# Main.net
KiCad netlist of a schematic drawn in EAGLE
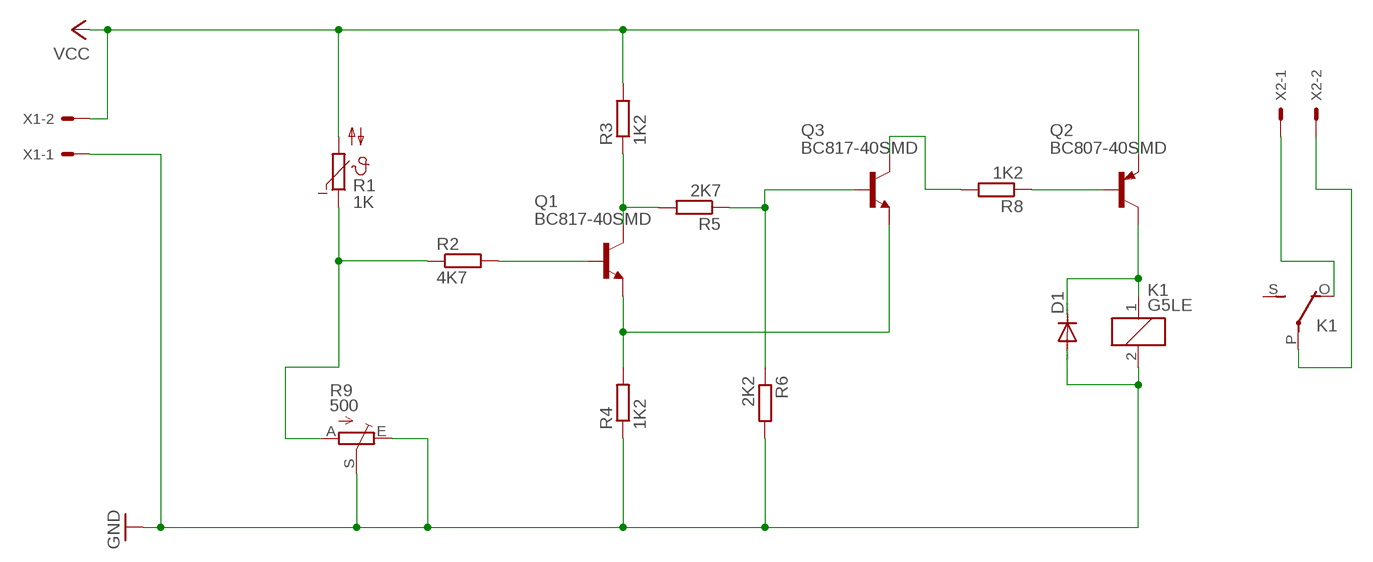
[diagram p0: schematic, sheet 1]

(export (version "E")
  (design (tool "Eeschema 10.0.6"))
  (components
    (comp (ref "D1")
      (value "DIODE-DO214AC")
      (footprint "eagle-import:DO214AC")
      (libsource (lib "eagle-import") (part "DIODE-DO214AC"))
    )
    (comp (ref "K1")
      (value "G5LE")
      (footprint "eagle-import:G5LE")
      (libsource (lib "eagle-import") (part "G5LE"))
    )
    (comp (ref "Q1")
      (value "BC817-40SMD")
      (footprint "eagle-import:SOT23-BEC")
      (libsource (lib "eagle-import") (part "BC817SMD-40"))
    )
    (comp (ref "Q2")
      (value "BC807-40SMD")
      (footprint "eagle-import:SOT23-BEC")
      (libsource (lib "eagle-import") (part "BC807SMD-40"))
    )
    (comp (ref "Q3")
      (value "BC817-40SMD")
      (footprint "eagle-import:SOT23-BEC")
      (libsource (lib "eagle-import") (part "BC817SMD-40"))
    )
    (comp (ref "R1")
      (value "1K")
      (footprint "eagle-import:B57164")
      (fields (field (name "MPN") "B57164K474K52"))
      (libsource (lib "eagle-import") (part "B57164"))
    )
    (comp (ref "R2")
      (value "4K7")
      (footprint "eagle-import:R1206")
      (libsource (lib "eagle-import") (part "R-EU_R1206"))
    )
    (comp (ref "R3")
      (value "1K2")
      (footprint "eagle-import:R1206")
      (libsource (lib "eagle-import") (part "R-EU_R1206"))
    )
    (comp (ref "R4")
      (value "1K2")
      (footprint "eagle-import:R1206")
      (libsource (lib "eagle-import") (part "R-EU_R1206"))
    )
    (comp (ref "R5")
      (value "2K7")
      (footprint "eagle-import:R1206")
      (libsource (lib "eagle-import") (part "R-EU_R1206"))
    )
    (comp (ref "R6")
      (value "2K2")
      (footprint "eagle-import:R1206")
      (libsource (lib "eagle-import") (part "R-EU_R1206"))
    )
    (comp (ref "R8")
      (value "1K2")
      (footprint "eagle-import:R1206")
      (libsource (lib "eagle-import") (part "R-EU_R1206"))
    )
    (comp (ref "R9")
      (value "500")
      (footprint "eagle-import:CA14V")
      (libsource (lib "eagle-import") (part "TRIM_EU-CA14V"))
    )
    (comp (ref "X1")
      (value "KK-156-2")
      (footprint "eagle-import:KK-156-2")
      (libsource (lib "eagle-import") (part "KK-156-2"))
    )
    (comp (ref "X2")
      (value "KK-156-2")
      (footprint "eagle-import:KK-156-2")
      (libsource (lib "eagle-import") (part "KK-156-2"))
    )
  )
  (nets
    (net (code "1") (name "GND") (class "Default")
      (node (ref "D1") (pin "A") (pinfunction "A_A") (pintype "passive"))
      (node (ref "K1") (pin "2") (pinfunction "2_2") (pintype "passive"))
      (node (ref "R4") (pin "1") (pinfunction "1_1") (pintype "passive"))
      (node (ref "R6") (pin "2") (pinfunction "2_2") (pintype "passive"))
      (node (ref "R9") (pin "E") (pinfunction "E_E") (pintype "passive"))
      (node (ref "R9") (pin "S") (pinfunction "S_S") (pintype "passive"))
      (node (ref "X1") (pin "1") (pinfunction "S_1") (pintype "passive"))
    )
    (net (code "2") (name "Net-(D1-PadC)") (class "Default")
      (node (ref "D1") (pin "C") (pinfunction "C_C") (pintype "passive"))
      (node (ref "K1") (pin "1") (pinfunction "1_1") (pintype "passive"))
      (node (ref "Q2") (pin "C") (pinfunction "C_C") (pintype "passive"))
    )
    (net (code "3") (name "Net-(Q1-PadB)") (class "Default")
      (node (ref "Q1") (pin "B") (pinfunction "B_B") (pintype "passive"))
      (node (ref "R2") (pin "2") (pinfunction "2_2") (pintype "passive"))
    )
    (net (code "4") (name "Net-(Q1-PadC)") (class "Default")
      (node (ref "Q1") (pin "C") (pinfunction "C_C") (pintype "passive"))
      (node (ref "R3") (pin "1") (pinfunction "1_1") (pintype "passive"))
      (node (ref "R5") (pin "2") (pinfunction "2_2") (pintype "passive"))
    )
    (net (code "5") (name "Net-(Q1-PadE)") (class "Default")
      (node (ref "Q1") (pin "E") (pinfunction "E_E") (pintype "passive"))
      (node (ref "Q3") (pin "E") (pinfunction "E_E") (pintype "passive"))
      (node (ref "R4") (pin "2") (pinfunction "2_2") (pintype "passive"))
    )
    (net (code "6") (name "Net-(Q2-PadB)") (class "Default")
      (node (ref "Q2") (pin "B") (pinfunction "B_B") (pintype "passive"))
      (node (ref "R8") (pin "1") (pinfunction "1_1") (pintype "passive"))
    )
    (net (code "7") (name "Net-(Q3-PadB)") (class "Default")
      (node (ref "Q3") (pin "B") (pinfunction "B_B") (pintype "passive"))
      (node (ref "R5") (pin "1") (pinfunction "1_1") (pintype "passive"))
      (node (ref "R6") (pin "1") (pinfunction "1_1") (pintype "passive"))
    )
    (net (code "8") (name "Net-(Q3-PadC)") (class "Default")
      (node (ref "Q3") (pin "C") (pinfunction "C_C") (pintype "passive"))
      (node (ref "R8") (pin "2") (pinfunction "2_2") (pintype "passive"))
    )
    (net (code "9") (name "Net-(R1-Pad1)") (class "Default")
      (node (ref "R1") (pin "1") (pinfunction "1_1") (pintype "passive"))
      (node (ref "R2") (pin "1") (pinfunction "1_1") (pintype "passive"))
      (node (ref "R9") (pin "A") (pinfunction "A_A") (pintype "passive"))
    )
    (net (code "10") (name "Net-(X2A-S)") (class "Default")
      (node (ref "K1") (pin "O") (pinfunction "O_O") (pintype "passive"))
      (node (ref "X2") (pin "1") (pinfunction "S_1") (pintype "passive"))
    )
    (net (code "11") (name "Net-(X2B-S)") (class "Default")
      (node (ref "K1") (pin "P") (pinfunction "P_P") (pintype "passive"))
      (node (ref "X2") (pin "2") (pinfunction "S_2") (pintype "passive"))
    )
    (net (code "12") (name "VCC") (class "Default")
      (node (ref "Q2") (pin "E") (pinfunction "E_E") (pintype "passive"))
      (node (ref "R1") (pin "2") (pinfunction "2_2") (pintype "passive"))
      (node (ref "R3") (pin "2") (pinfunction "2_2") (pintype "passive"))
      (node (ref "X1") (pin "2") (pinfunction "S_2") (pintype "passive"))
    )
    (net (code "13") (name "unconnected-(K1-PadS)") (class "Default")
      (node (ref "K1") (pin "S") (pinfunction "S_S") (pintype "passive"))
    )
  )
)
